# horizontal_driver.net
KiCad netlist of a schematic drawn in EAGLE
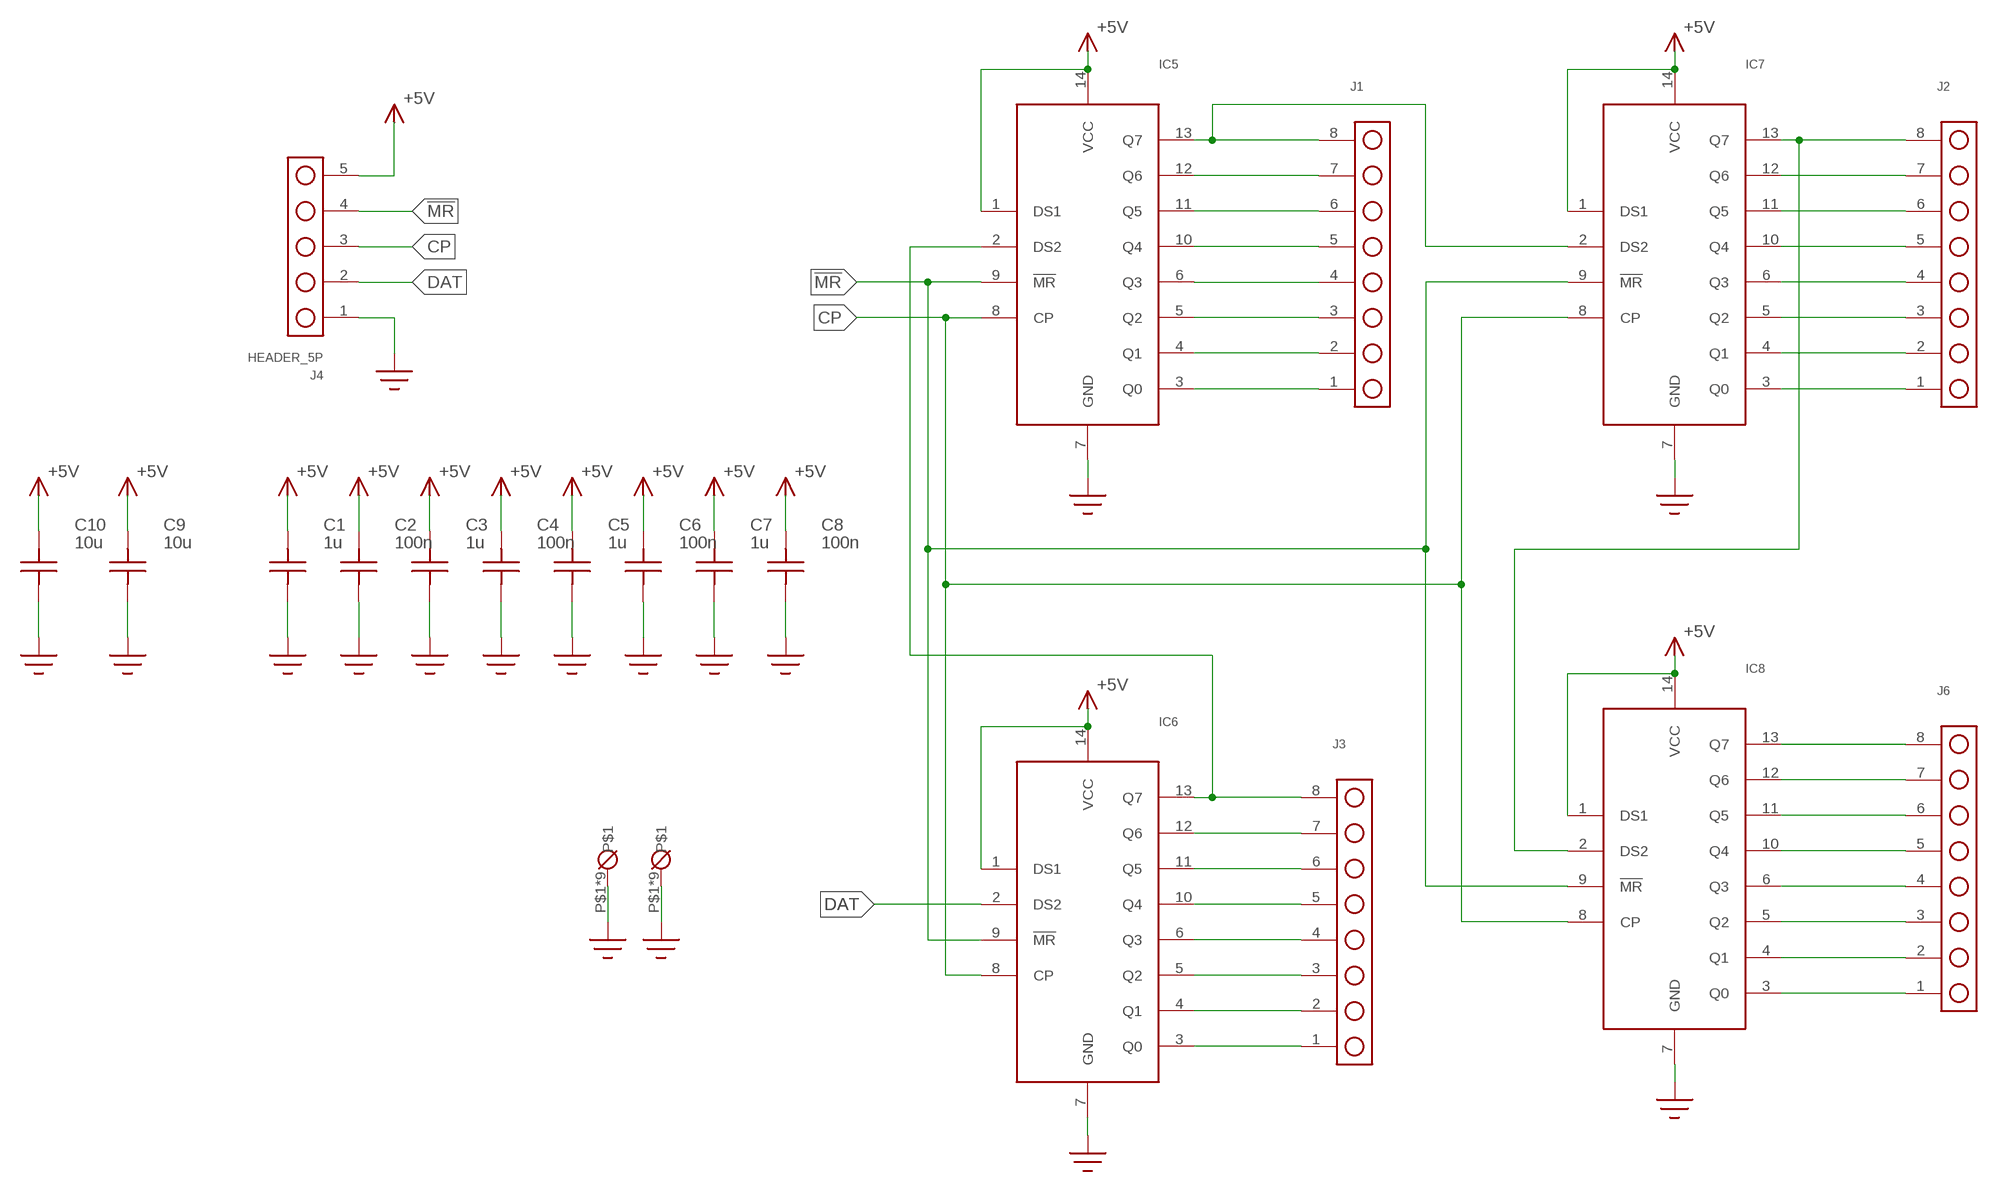
[diagram p0: schematic, sheet 1]

(export (version "E")
  (design (tool "Eeschema 10.0.6"))
  (components
    (comp (ref "C1")
      (value "1u")
      (footprint "eagle-import:0805")
      (libsource (lib "eagle-import") (part "C0805"))
    )
    (comp (ref "C2")
      (value "100n")
      (footprint "eagle-import:0805")
      (libsource (lib "eagle-import") (part "C0805"))
    )
    (comp (ref "C3")
      (value "1u")
      (footprint "eagle-import:0805")
      (libsource (lib "eagle-import") (part "C0805"))
    )
    (comp (ref "C4")
      (value "100n")
      (footprint "eagle-import:0805")
      (libsource (lib "eagle-import") (part "C0805"))
    )
    (comp (ref "C5")
      (value "1u")
      (footprint "eagle-import:0805")
      (libsource (lib "eagle-import") (part "C0805"))
    )
    (comp (ref "C6")
      (value "100n")
      (footprint "eagle-import:0805")
      (libsource (lib "eagle-import") (part "C0805"))
    )
    (comp (ref "C7")
      (value "1u")
      (footprint "eagle-import:0805")
      (libsource (lib "eagle-import") (part "C0805"))
    )
    (comp (ref "C8")
      (value "100n")
      (footprint "eagle-import:0805")
      (libsource (lib "eagle-import") (part "C0805"))
    )
    (comp (ref "C9")
      (value "10u")
      (footprint "eagle-import:1206")
      (libsource (lib "eagle-import") (part "C1206"))
    )
    (comp (ref "C10")
      (value "10u")
      (footprint "eagle-import:1206")
      (libsource (lib "eagle-import") (part "C1206"))
    )
    (comp (ref "IC5")
      (value "74XX164")
      (footprint "eagle-import:SOIC-14")
      (libsource (lib "eagle-import") (part "74XX164"))
    )
    (comp (ref "IC6")
      (value "74XX164")
      (footprint "eagle-import:SOIC-14")
      (libsource (lib "eagle-import") (part "74XX164"))
    )
    (comp (ref "IC7")
      (value "74XX164")
      (footprint "eagle-import:SOIC-14")
      (libsource (lib "eagle-import") (part "74XX164"))
    )
    (comp (ref "IC8")
      (value "74XX164")
      (footprint "eagle-import:SOIC-14")
      (libsource (lib "eagle-import") (part "74XX164"))
    )
    (comp (ref "J1")
      (value "HEADER_8P")
      (footprint "eagle-import:HEADER_8P")
      (libsource (lib "eagle-import") (part "HEADER_8P"))
    )
    (comp (ref "J2")
      (value "HEADER_8P")
      (footprint "eagle-import:HEADER_8P")
      (libsource (lib "eagle-import") (part "HEADER_8P"))
    )
    (comp (ref "J3")
      (value "HEADER_8P")
      (footprint "eagle-import:HEADER_8P")
      (libsource (lib "eagle-import") (part "HEADER_8P"))
    )
    (comp (ref "J4")
      (value "HEADER_5P")
      (footprint "eagle-import:HEADER_5P")
      (libsource (lib "eagle-import") (part "HEADER_5P"))
    )
    (comp (ref "J6")
      (value "HEADER_8P")
      (footprint "eagle-import:HEADER_8P")
      (libsource (lib "eagle-import") (part "HEADER_8P"))
    )
    (comp (ref "U$1")
      (value "MOUNTING_HOLE")
      (footprint "eagle-import:MOUNTING_HOLE_#4")
      (libsource (lib "eagle-import") (part "MOUNTING_HOLE"))
    )
    (comp (ref "U$2")
      (value "MOUNTING_HOLE")
      (footprint "eagle-import:MOUNTING_HOLE_#4")
      (libsource (lib "eagle-import") (part "MOUNTING_HOLE"))
    )
  )
  (nets
    (net (code "1") (name "+5V") (class "Default")
      (node (ref "C1") (pin "P$2") (pinfunction "P$2_P$2") (pintype "bidirectional"))
      (node (ref "C10") (pin "P$2") (pinfunction "P$2_P$2") (pintype "bidirectional"))
      (node (ref "C2") (pin "P$2") (pinfunction "P$2_P$2") (pintype "bidirectional"))
      (node (ref "C3") (pin "P$2") (pinfunction "P$2_P$2") (pintype "bidirectional"))
      (node (ref "C4") (pin "P$2") (pinfunction "P$2_P$2") (pintype "bidirectional"))
      (node (ref "C5") (pin "P$2") (pinfunction "P$2_P$2") (pintype "bidirectional"))
      (node (ref "C6") (pin "P$2") (pinfunction "P$2_P$2") (pintype "bidirectional"))
      (node (ref "C7") (pin "P$2") (pinfunction "P$2_P$2") (pintype "bidirectional"))
      (node (ref "C8") (pin "P$2") (pinfunction "P$2_P$2") (pintype "bidirectional"))
      (node (ref "C9") (pin "P$2") (pinfunction "P$2_P$2") (pintype "bidirectional"))
      (node (ref "IC5") (pin "1") (pinfunction "DS1_1") (pintype "bidirectional"))
      (node (ref "IC5") (pin "14") (pinfunction "VCC_14") (pintype "bidirectional"))
      (node (ref "IC6") (pin "1") (pinfunction "DS1_1") (pintype "bidirectional"))
      (node (ref "IC6") (pin "14") (pinfunction "VCC_14") (pintype "bidirectional"))
      (node (ref "IC7") (pin "1") (pinfunction "DS1_1") (pintype "bidirectional"))
      (node (ref "IC7") (pin "14") (pinfunction "VCC_14") (pintype "bidirectional"))
      (node (ref "IC8") (pin "1") (pinfunction "DS1_1") (pintype "bidirectional"))
      (node (ref "IC8") (pin "14") (pinfunction "VCC_14") (pintype "bidirectional"))
      (node (ref "J4") (pin "5") (pinfunction "5_5") (pintype "bidirectional"))
    )
    (net (code "2") (name "/~{MR}") (class "Default")
      (node (ref "IC5") (pin "9") (pinfunction "~{MR}_9") (pintype "bidirectional"))
      (node (ref "IC6") (pin "9") (pinfunction "~{MR}_9") (pintype "bidirectional"))
      (node (ref "IC7") (pin "9") (pinfunction "~{MR}_9") (pintype "bidirectional"))
      (node (ref "IC8") (pin "9") (pinfunction "~{MR}_9") (pintype "bidirectional"))
      (node (ref "J4") (pin "4") (pinfunction "4_4") (pintype "bidirectional"))
    )
    (net (code "3") (name "CP") (class "Default")
      (node (ref "IC5") (pin "8") (pinfunction "CP_8") (pintype "bidirectional"))
      (node (ref "IC6") (pin "8") (pinfunction "CP_8") (pintype "bidirectional"))
      (node (ref "IC7") (pin "8") (pinfunction "CP_8") (pintype "bidirectional"))
      (node (ref "IC8") (pin "8") (pinfunction "CP_8") (pintype "bidirectional"))
      (node (ref "J4") (pin "3") (pinfunction "3_3") (pintype "bidirectional"))
    )
    (net (code "4") (name "DAT") (class "Default")
      (node (ref "IC6") (pin "2") (pinfunction "DS2_2") (pintype "bidirectional"))
      (node (ref "J4") (pin "2") (pinfunction "2_2") (pintype "bidirectional"))
    )
    (net (code "5") (name "GND") (class "Default")
      (node (ref "C1") (pin "P$1") (pinfunction "P$1_P$1") (pintype "bidirectional"))
      (node (ref "C10") (pin "P$1") (pinfunction "P$1_P$1") (pintype "bidirectional"))
      (node (ref "C2") (pin "P$1") (pinfunction "P$1_P$1") (pintype "bidirectional"))
      (node (ref "C3") (pin "P$1") (pinfunction "P$1_P$1") (pintype "bidirectional"))
      (node (ref "C4") (pin "P$1") (pinfunction "P$1_P$1") (pintype "bidirectional"))
      (node (ref "C5") (pin "P$1") (pinfunction "P$1_P$1") (pintype "bidirectional"))
      (node (ref "C6") (pin "P$1") (pinfunction "P$1_P$1") (pintype "bidirectional"))
      (node (ref "C7") (pin "P$1") (pinfunction "P$1_P$1") (pintype "bidirectional"))
      (node (ref "C8") (pin "P$1") (pinfunction "P$1_P$1") (pintype "bidirectional"))
      (node (ref "C9") (pin "P$1") (pinfunction "P$1_P$1") (pintype "bidirectional"))
      (node (ref "IC5") (pin "7") (pinfunction "GND_7") (pintype "bidirectional"))
      (node (ref "IC6") (pin "7") (pinfunction "GND_7") (pintype "bidirectional"))
      (node (ref "IC7") (pin "7") (pinfunction "GND_7") (pintype "bidirectional"))
      (node (ref "IC8") (pin "7") (pinfunction "GND_7") (pintype "bidirectional"))
      (node (ref "J4") (pin "1") (pinfunction "1_1") (pintype "bidirectional"))
      (node (ref "U$1") (pin "P$1") (pinfunction "P$1_P$1") (pintype "bidirectional"))
      (node (ref "U$1") (pin "P$2") (pinfunction "P$1_P$2") (pintype "bidirectional"))
      (node (ref "U$1") (pin "P$3") (pinfunction "P$1_P$3") (pintype "bidirectional"))
      (node (ref "U$1") (pin "P$4") (pinfunction "P$1_P$4") (pintype "bidirectional"))
      (node (ref "U$1") (pin "P$5") (pinfunction "P$1_P$5") (pintype "bidirectional"))
      (node (ref "U$1") (pin "P$6") (pinfunction "P$1_P$6") (pintype "bidirectional"))
      (node (ref "U$1") (pin "P$7") (pinfunction "P$1_P$7") (pintype "bidirectional"))
      (node (ref "U$1") (pin "P$8") (pinfunction "P$1_P$8") (pintype "bidirectional"))
      (node (ref "U$1") (pin "P$9") (pinfunction "P$1_P$9") (pintype "bidirectional"))
      (node (ref "U$2") (pin "P$1") (pinfunction "P$1_P$1") (pintype "bidirectional"))
      (node (ref "U$2") (pin "P$2") (pinfunction "P$1_P$2") (pintype "bidirectional"))
      (node (ref "U$2") (pin "P$3") (pinfunction "P$1_P$3") (pintype "bidirectional"))
      (node (ref "U$2") (pin "P$4") (pinfunction "P$1_P$4") (pintype "bidirectional"))
      (node (ref "U$2") (pin "P$5") (pinfunction "P$1_P$5") (pintype "bidirectional"))
      (node (ref "U$2") (pin "P$6") (pinfunction "P$1_P$6") (pintype "bidirectional"))
      (node (ref "U$2") (pin "P$7") (pinfunction "P$1_P$7") (pintype "bidirectional"))
      (node (ref "U$2") (pin "P$8") (pinfunction "P$1_P$8") (pintype "bidirectional"))
      (node (ref "U$2") (pin "P$9") (pinfunction "P$1_P$9") (pintype "bidirectional"))
    )
    (net (code "6") (name "Net-(IC5-DS2)") (class "Default")
      (node (ref "IC5") (pin "2") (pinfunction "DS2_2") (pintype "bidirectional"))
      (node (ref "IC6") (pin "13") (pinfunction "Q7_13") (pintype "bidirectional"))
      (node (ref "J3") (pin "8") (pinfunction "8_8") (pintype "bidirectional"))
    )
    (net (code "7") (name "Net-(IC5-Q0)") (class "Default")
      (node (ref "IC5") (pin "3") (pinfunction "Q0_3") (pintype "bidirectional"))
      (node (ref "J1") (pin "1") (pinfunction "1_1") (pintype "bidirectional"))
    )
    (net (code "8") (name "Net-(IC5-Q1)") (class "Default")
      (node (ref "IC5") (pin "4") (pinfunction "Q1_4") (pintype "bidirectional"))
      (node (ref "J1") (pin "2") (pinfunction "2_2") (pintype "bidirectional"))
    )
    (net (code "9") (name "Net-(IC5-Q2)") (class "Default")
      (node (ref "IC5") (pin "5") (pinfunction "Q2_5") (pintype "bidirectional"))
      (node (ref "J1") (pin "3") (pinfunction "3_3") (pintype "bidirectional"))
    )
    (net (code "10") (name "Net-(IC5-Q3)") (class "Default")
      (node (ref "IC5") (pin "6") (pinfunction "Q3_6") (pintype "bidirectional"))
      (node (ref "J1") (pin "4") (pinfunction "4_4") (pintype "bidirectional"))
    )
    (net (code "11") (name "Net-(IC5-Q4)") (class "Default")
      (node (ref "IC5") (pin "10") (pinfunction "Q4_10") (pintype "bidirectional"))
      (node (ref "J1") (pin "5") (pinfunction "5_5") (pintype "bidirectional"))
    )
    (net (code "12") (name "Net-(IC5-Q5)") (class "Default")
      (node (ref "IC5") (pin "11") (pinfunction "Q5_11") (pintype "bidirectional"))
      (node (ref "J1") (pin "6") (pinfunction "6_6") (pintype "bidirectional"))
    )
    (net (code "13") (name "Net-(IC5-Q6)") (class "Default")
      (node (ref "IC5") (pin "12") (pinfunction "Q6_12") (pintype "bidirectional"))
      (node (ref "J1") (pin "7") (pinfunction "7_7") (pintype "bidirectional"))
    )
    (net (code "14") (name "Net-(IC5-Q7)") (class "Default")
      (node (ref "IC5") (pin "13") (pinfunction "Q7_13") (pintype "bidirectional"))
      (node (ref "IC7") (pin "2") (pinfunction "DS2_2") (pintype "bidirectional"))
      (node (ref "J1") (pin "8") (pinfunction "8_8") (pintype "bidirectional"))
    )
    (net (code "15") (name "Net-(IC6-Q0)") (class "Default")
      (node (ref "IC6") (pin "3") (pinfunction "Q0_3") (pintype "bidirectional"))
      (node (ref "J3") (pin "1") (pinfunction "1_1") (pintype "bidirectional"))
    )
    (net (code "16") (name "Net-(IC6-Q1)") (class "Default")
      (node (ref "IC6") (pin "4") (pinfunction "Q1_4") (pintype "bidirectional"))
      (node (ref "J3") (pin "2") (pinfunction "2_2") (pintype "bidirectional"))
    )
    (net (code "17") (name "Net-(IC6-Q2)") (class "Default")
      (node (ref "IC6") (pin "5") (pinfunction "Q2_5") (pintype "bidirectional"))
      (node (ref "J3") (pin "3") (pinfunction "3_3") (pintype "bidirectional"))
    )
    (net (code "18") (name "Net-(IC6-Q3)") (class "Default")
      (node (ref "IC6") (pin "6") (pinfunction "Q3_6") (pintype "bidirectional"))
      (node (ref "J3") (pin "4") (pinfunction "4_4") (pintype "bidirectional"))
    )
    (net (code "19") (name "Net-(IC6-Q4)") (class "Default")
      (node (ref "IC6") (pin "10") (pinfunction "Q4_10") (pintype "bidirectional"))
      (node (ref "J3") (pin "5") (pinfunction "5_5") (pintype "bidirectional"))
    )
    (net (code "20") (name "Net-(IC6-Q5)") (class "Default")
      (node (ref "IC6") (pin "11") (pinfunction "Q5_11") (pintype "bidirectional"))
      (node (ref "J3") (pin "6") (pinfunction "6_6") (pintype "bidirectional"))
    )
    (net (code "21") (name "Net-(IC6-Q6)") (class "Default")
      (node (ref "IC6") (pin "12") (pinfunction "Q6_12") (pintype "bidirectional"))
      (node (ref "J3") (pin "7") (pinfunction "7_7") (pintype "bidirectional"))
    )
    (net (code "22") (name "Net-(IC7-Q0)") (class "Default")
      (node (ref "IC7") (pin "3") (pinfunction "Q0_3") (pintype "bidirectional"))
      (node (ref "J2") (pin "1") (pinfunction "1_1") (pintype "bidirectional"))
    )
    (net (code "23") (name "Net-(IC7-Q1)") (class "Default")
      (node (ref "IC7") (pin "4") (pinfunction "Q1_4") (pintype "bidirectional"))
      (node (ref "J2") (pin "2") (pinfunction "2_2") (pintype "bidirectional"))
    )
    (net (code "24") (name "Net-(IC7-Q2)") (class "Default")
      (node (ref "IC7") (pin "5") (pinfunction "Q2_5") (pintype "bidirectional"))
      (node (ref "J2") (pin "3") (pinfunction "3_3") (pintype "bidirectional"))
    )
    (net (code "25") (name "Net-(IC7-Q3)") (class "Default")
      (node (ref "IC7") (pin "6") (pinfunction "Q3_6") (pintype "bidirectional"))
      (node (ref "J2") (pin "4") (pinfunction "4_4") (pintype "bidirectional"))
    )
    (net (code "26") (name "Net-(IC7-Q4)") (class "Default")
      (node (ref "IC7") (pin "10") (pinfunction "Q4_10") (pintype "bidirectional"))
      (node (ref "J2") (pin "5") (pinfunction "5_5") (pintype "bidirectional"))
    )
    (net (code "27") (name "Net-(IC7-Q5)") (class "Default")
      (node (ref "IC7") (pin "11") (pinfunction "Q5_11") (pintype "bidirectional"))
      (node (ref "J2") (pin "6") (pinfunction "6_6") (pintype "bidirectional"))
    )
    (net (code "28") (name "Net-(IC7-Q6)") (class "Default")
      (node (ref "IC7") (pin "12") (pinfunction "Q6_12") (pintype "bidirectional"))
      (node (ref "J2") (pin "7") (pinfunction "7_7") (pintype "bidirectional"))
    )
    (net (code "29") (name "Net-(IC7-Q7)") (class "Default")
      (node (ref "IC7") (pin "13") (pinfunction "Q7_13") (pintype "bidirectional"))
      (node (ref "IC8") (pin "2") (pinfunction "DS2_2") (pintype "bidirectional"))
      (node (ref "J2") (pin "8") (pinfunction "8_8") (pintype "bidirectional"))
    )
    (net (code "30") (name "Net-(IC8-Q0)") (class "Default")
      (node (ref "IC8") (pin "3") (pinfunction "Q0_3") (pintype "bidirectional"))
      (node (ref "J6") (pin "1") (pinfunction "1_1") (pintype "bidirectional"))
    )
    (net (code "31") (name "Net-(IC8-Q1)") (class "Default")
      (node (ref "IC8") (pin "4") (pinfunction "Q1_4") (pintype "bidirectional"))
      (node (ref "J6") (pin "2") (pinfunction "2_2") (pintype "bidirectional"))
    )
    (net (code "32") (name "Net-(IC8-Q2)") (class "Default")
      (node (ref "IC8") (pin "5") (pinfunction "Q2_5") (pintype "bidirectional"))
      (node (ref "J6") (pin "3") (pinfunction "3_3") (pintype "bidirectional"))
    )
    (net (code "33") (name "Net-(IC8-Q3)") (class "Default")
      (node (ref "IC8") (pin "6") (pinfunction "Q3_6") (pintype "bidirectional"))
      (node (ref "J6") (pin "4") (pinfunction "4_4") (pintype "bidirectional"))
    )
    (net (code "34") (name "Net-(IC8-Q4)") (class "Default")
      (node (ref "IC8") (pin "10") (pinfunction "Q4_10") (pintype "bidirectional"))
      (node (ref "J6") (pin "5") (pinfunction "5_5") (pintype "bidirectional"))
    )
    (net (code "35") (name "Net-(IC8-Q5)") (class "Default")
      (node (ref "IC8") (pin "11") (pinfunction "Q5_11") (pintype "bidirectional"))
      (node (ref "J6") (pin "6") (pinfunction "6_6") (pintype "bidirectional"))
    )
    (net (code "36") (name "Net-(IC8-Q6)") (class "Default")
      (node (ref "IC8") (pin "12") (pinfunction "Q6_12") (pintype "bidirectional"))
      (node (ref "J6") (pin "7") (pinfunction "7_7") (pintype "bidirectional"))
    )
    (net (code "37") (name "Net-(IC8-Q7)") (class "Default")
      (node (ref "IC8") (pin "13") (pinfunction "Q7_13") (pintype "bidirectional"))
      (node (ref "J6") (pin "8") (pinfunction "8_8") (pintype "bidirectional"))
    )
  )
)
